# tb6612fng.net
KiCad netlist of a schematic drawn in Altium Designer
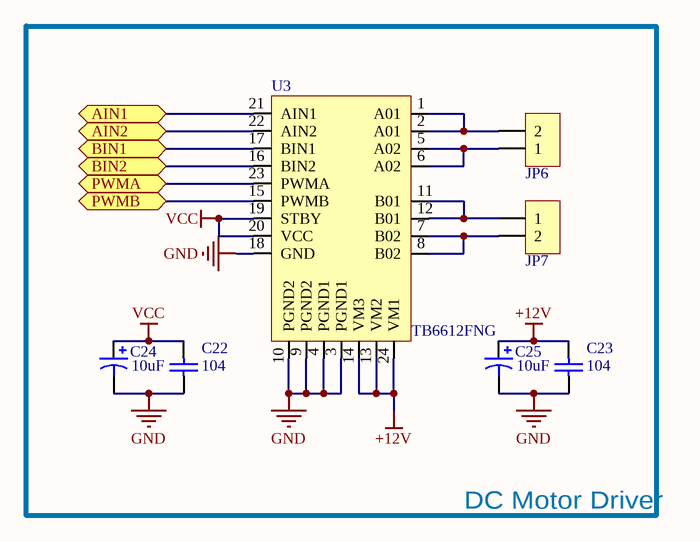
[diagram p0: tb6612fng.SchDoc]

(export (version "E")
  (design (tool "Eeschema 10.0.6"))
  (components
    (comp (ref "C22")
      (value "104")
      (footprint "C 0603_L")
      (description "Capacitor")
      (fields (field (name "PUBLISHER") "Altium Limited"))
      (libsource (lib "Miscellaneous Devices") (part "Cap"))
    )
    (comp (ref "C23")
      (value "104")
      (footprint "C 0603_L")
      (description "Capacitor")
      (fields (field (name "PUBLISHER") "Altium Limited"))
      (libsource (lib "Miscellaneous Devices") (part "Cap"))
    )
    (comp (ref "C24")
      (value "10uF")
      (footprint "CD A(3216)")
      (description "Polarized Capacitor (Radial)")
      (fields (field (name "PUBLISHER") "Altium Limited"))
      (libsource (lib "Miscellaneous Devices") (part "Cap Pol1"))
    )
    (comp (ref "C25")
      (value "10uF")
      (footprint "CD A(3216)")
      (description "Polarized Capacitor (Radial)")
      (fields (field (name "PUBLISHER") "Altium Limited"))
      (libsource (lib "Miscellaneous Devices") (part "Cap Pol1"))
    )
    (comp (ref "JP6")
      (value "HDR-1X2")
      (footprint "XH2.54-LI-2P")
      (description "2P接插件")
      (fields (field (name "版权归属") "源创客"))
      (libsource (lib "") (part "Header 2_1"))
    )
    (comp (ref "JP7")
      (value "HDR-1X2")
      (footprint "XH2.54-LI-2P")
      (description "2P接插件")
      (fields (field (name "版权归属") "源创客"))
      (libsource (lib "4.5   - 接插件-脚距2.54") (part "Header 2"))
    )
    (comp (ref "U3")
      (value "TB6612FNG")
      (footprint "SSOP24_N")
      (description "DC_MOTOR_DRIVER")
      (libsource (lib "主控板载芯片") (part "TB6612FNG"))
    )
  )
  (nets
    (net (code "1") (name "+12V") (class "Default")
      (node (ref "C23") (pin "2") (pinfunction "2_2") (pintype "passive"))
      (node (ref "C25") (pin "1") (pinfunction "1_1") (pintype "passive"))
      (node (ref "U3") (pin "13") (pinfunction "VM2_13") (pintype "passive"))
      (node (ref "U3") (pin "14") (pinfunction "VM3_14") (pintype "passive"))
      (node (ref "U3") (pin "24") (pinfunction "VM1_24") (pintype "passive"))
    )
    (net (code "2") (name "/AIN1") (class "Default")
      (node (ref "U3") (pin "21") (pinfunction "AIN1_21") (pintype "passive"))
    )
    (net (code "3") (name "/AIN2") (class "Default")
      (node (ref "U3") (pin "22") (pinfunction "AIN2_22") (pintype "passive"))
    )
    (net (code "4") (name "/BIN1") (class "Default")
      (node (ref "U3") (pin "17") (pinfunction "BIN1_17") (pintype "passive"))
    )
    (net (code "5") (name "/BIN2") (class "Default")
      (node (ref "U3") (pin "16") (pinfunction "BIN2_16") (pintype "passive"))
    )
    (net (code "6") (name "/PWMA") (class "Default")
      (node (ref "U3") (pin "23") (pinfunction "PWMA_23") (pintype "passive"))
    )
    (net (code "7") (name "/PWMB") (class "Default")
      (node (ref "U3") (pin "15") (pinfunction "PWMB_15") (pintype "passive"))
    )
    (net (code "8") (name "GND") (class "Default")
      (node (ref "C22") (pin "1") (pinfunction "1_1") (pintype "passive"))
      (node (ref "C23") (pin "1") (pinfunction "1_1") (pintype "passive"))
      (node (ref "C24") (pin "2") (pinfunction "2_2") (pintype "passive"))
      (node (ref "C25") (pin "2") (pinfunction "2_2") (pintype "passive"))
      (node (ref "U3") (pin "10") (pinfunction "PGND2_10") (pintype "passive"))
      (node (ref "U3") (pin "18") (pinfunction "GND_18") (pintype "passive"))
      (node (ref "U3") (pin "3") (pinfunction "PGND1_3") (pintype "passive"))
      (node (ref "U3") (pin "4") (pinfunction "PGND1_4") (pintype "passive"))
      (node (ref "U3") (pin "9") (pinfunction "PGND2_9") (pintype "passive"))
    )
    (net (code "9") (name "Net-(JP6-Pad1)") (class "Default")
      (node (ref "JP6") (pin "1") (pinfunction "1_1") (pintype "passive"))
      (node (ref "U3") (pin "5") (pinfunction "A02_5") (pintype "passive"))
      (node (ref "U3") (pin "6") (pinfunction "A02_6") (pintype "passive"))
    )
    (net (code "10") (name "Net-(JP6-Pad2)") (class "Default")
      (node (ref "JP6") (pin "2") (pinfunction "2_2") (pintype "passive"))
      (node (ref "U3") (pin "1") (pinfunction "A01_1") (pintype "passive"))
      (node (ref "U3") (pin "2") (pinfunction "A01_2") (pintype "passive"))
    )
    (net (code "11") (name "Net-(JP7-Pad1)") (class "Default")
      (node (ref "JP7") (pin "1") (pinfunction "1_1") (pintype "passive"))
      (node (ref "U3") (pin "11") (pinfunction "B01_11") (pintype "passive"))
      (node (ref "U3") (pin "12") (pinfunction "B01_12") (pintype "passive"))
    )
    (net (code "12") (name "Net-(JP7-Pad2)") (class "Default")
      (node (ref "JP7") (pin "2") (pinfunction "2_2") (pintype "passive"))
      (node (ref "U3") (pin "7") (pinfunction "B02_7") (pintype "passive"))
      (node (ref "U3") (pin "8") (pinfunction "B02_8") (pintype "passive"))
    )
    (net (code "13") (name "VCC") (class "Default")
      (node (ref "C22") (pin "2") (pinfunction "2_2") (pintype "passive"))
      (node (ref "C24") (pin "1") (pinfunction "1_1") (pintype "passive"))
      (node (ref "U3") (pin "19") (pinfunction "STBY_19") (pintype "passive"))
      (node (ref "U3") (pin "20") (pinfunction "VCC_20") (pintype "passive"))
    )
  )
)
